# bristol_longshot.net
KiCad netlist of a schematic drawn in EAGLE
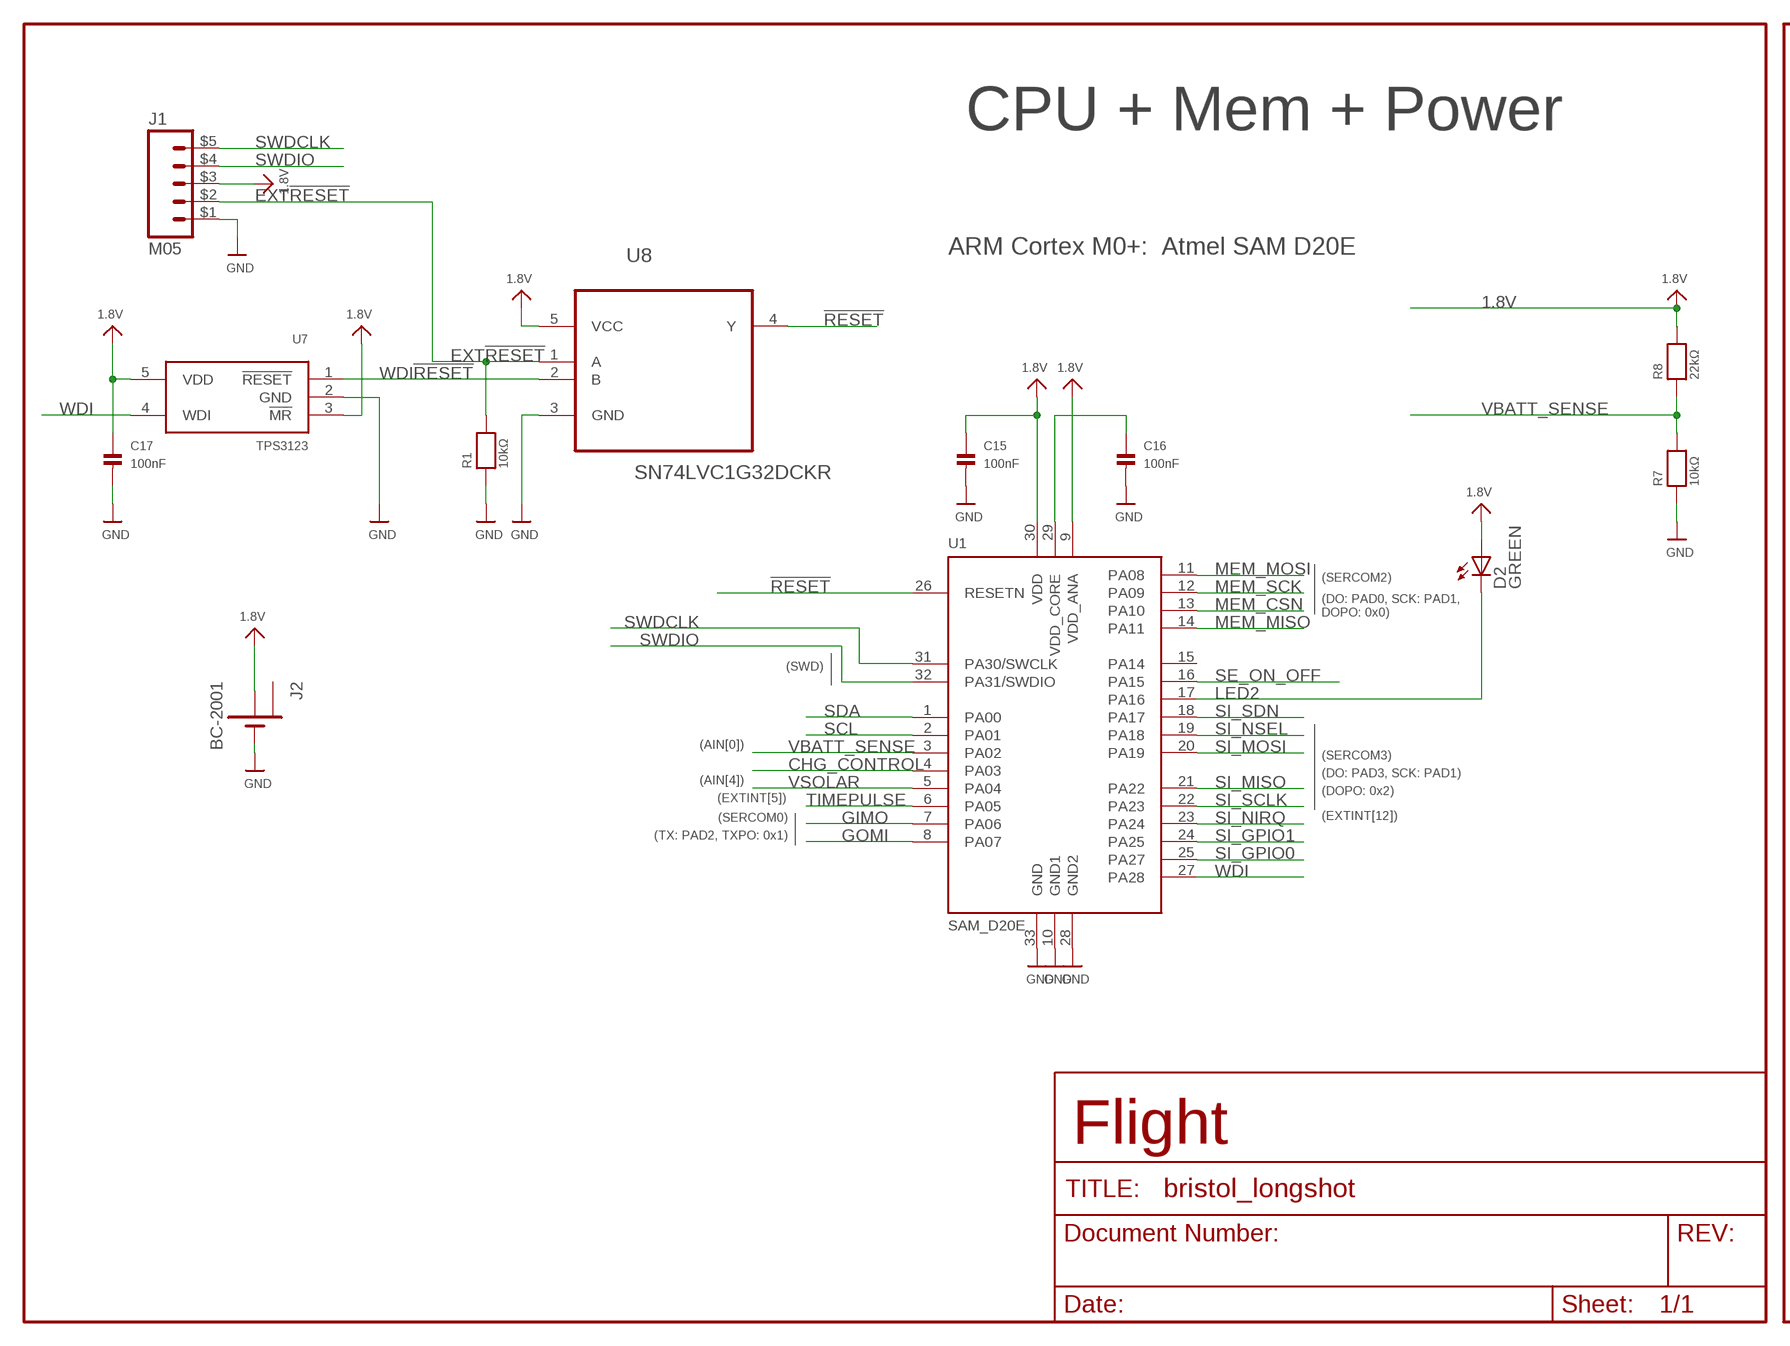
[diagram p0: schematic, sheet 1, part 1 of 2]
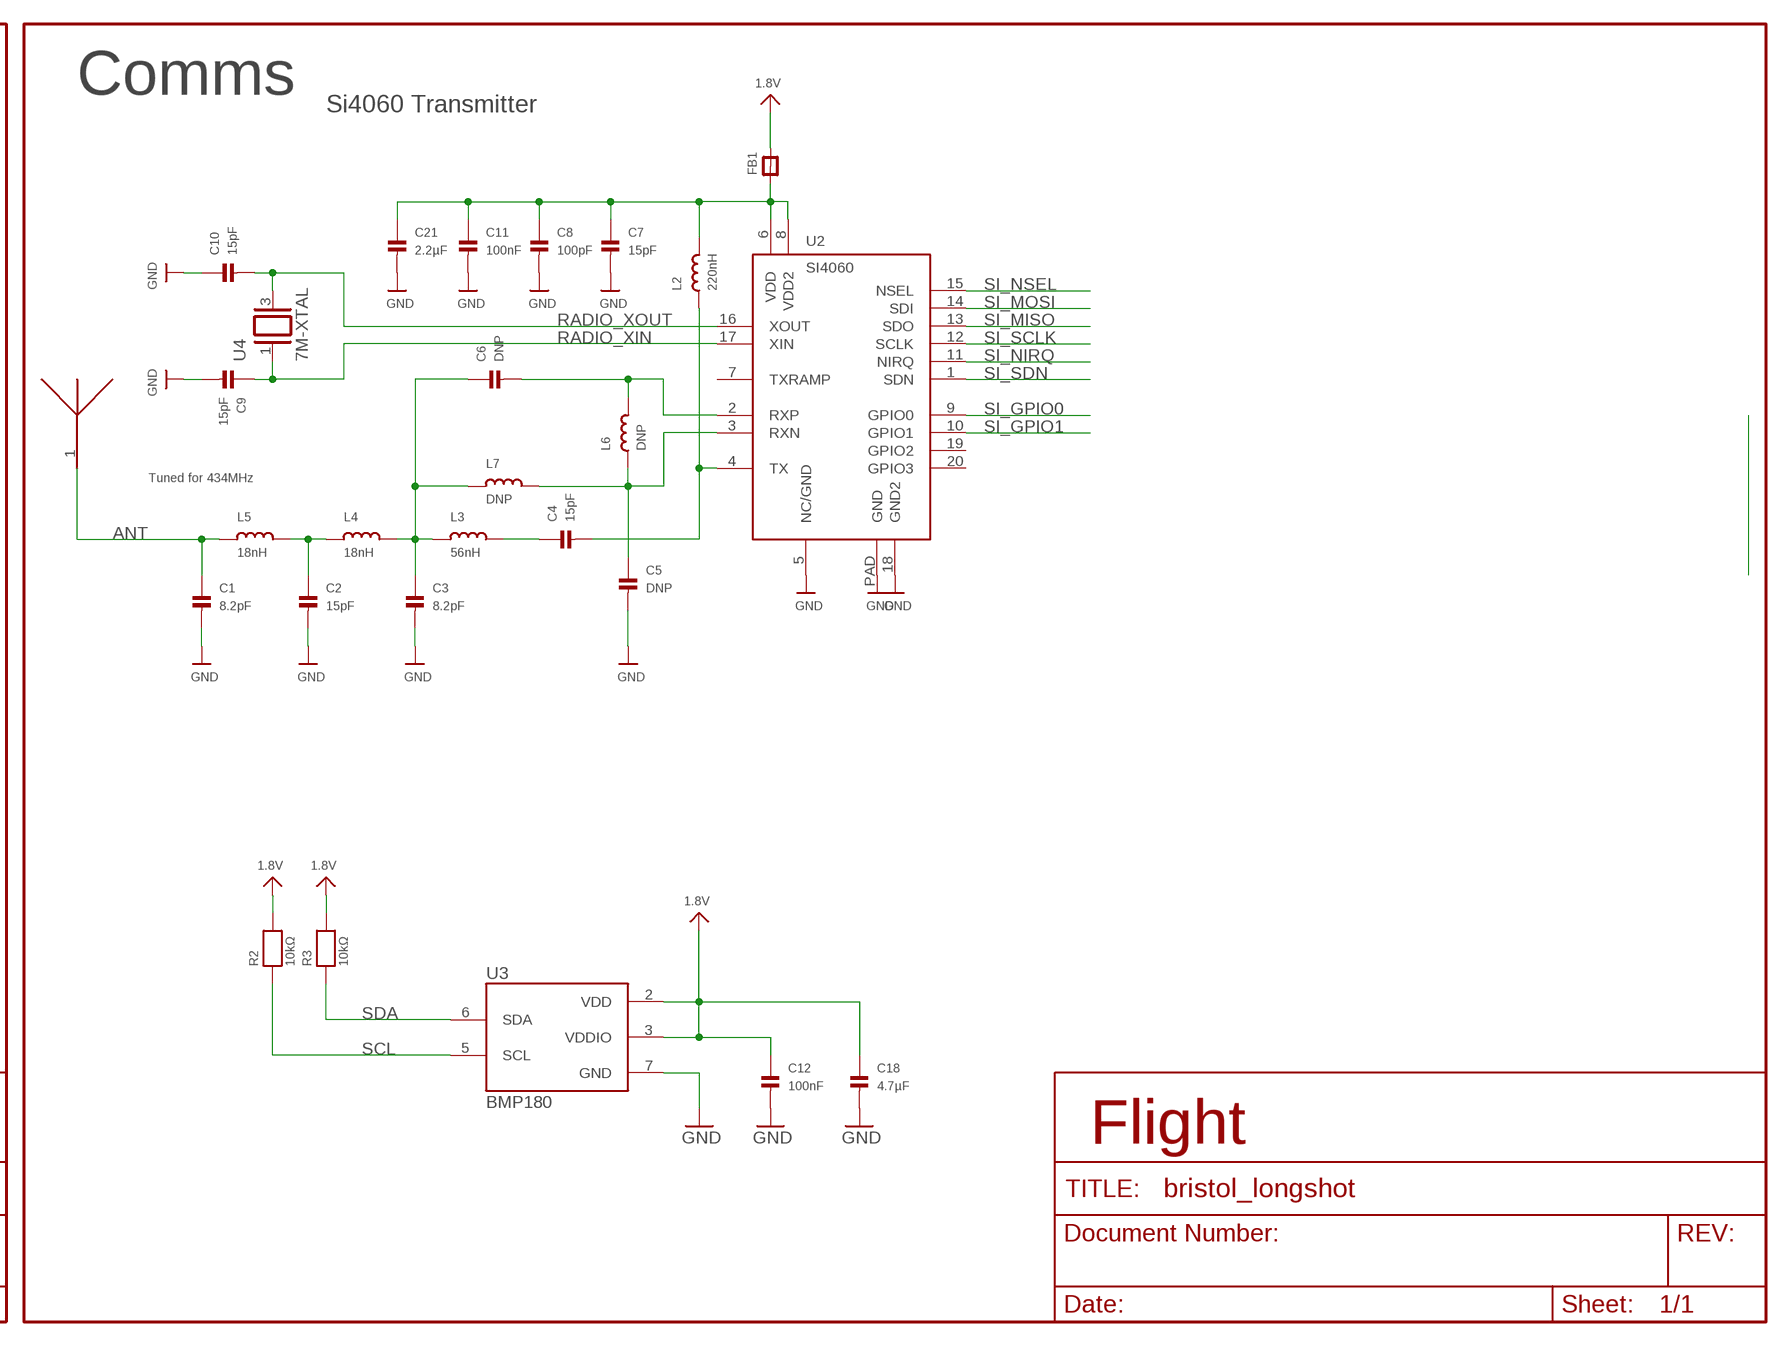
[diagram p1: schematic, sheet 1, part 2 of 2]

(export (version "E")
  (design (tool "Eeschema 10.0.6"))
  (components
    (comp (ref "C1")
      (value "8.2pF")
      (footprint "eagle-import:_0402")
      (libsource (lib "eagle-import") (part "CAP_CERAMIC_0402"))
    )
    (comp (ref "C2")
      (value "15pF")
      (footprint "eagle-import:_0402")
      (libsource (lib "eagle-import") (part "CAP_CERAMIC_0402"))
    )
    (comp (ref "C3")
      (value "8.2pF")
      (footprint "eagle-import:_0402")
      (libsource (lib "eagle-import") (part "CAP_CERAMIC_0402"))
    )
    (comp (ref "C4")
      (value "15pF")
      (footprint "eagle-import:_0402")
      (libsource (lib "eagle-import") (part "CAP_CERAMIC_0402"))
    )
    (comp (ref "C5")
      (value "DNP")
      (footprint "eagle-import:_0402")
      (libsource (lib "eagle-import") (part "CAP_CERAMIC_0402"))
    )
    (comp (ref "C6")
      (value "DNP")
      (footprint "eagle-import:_0402")
      (libsource (lib "eagle-import") (part "CAP_CERAMIC_0402"))
    )
    (comp (ref "C7")
      (value "15pF")
      (footprint "eagle-import:_0402")
      (libsource (lib "eagle-import") (part "CAP_CERAMIC_0402"))
    )
    (comp (ref "C8")
      (value "100pF")
      (footprint "eagle-import:_0402")
      (libsource (lib "eagle-import") (part "CAP_CERAMIC_0402"))
    )
    (comp (ref "C9")
      (value "15pF")
      (footprint "eagle-import:_0402")
      (libsource (lib "eagle-import") (part "CAP_CERAMIC_0402"))
    )
    (comp (ref "C10")
      (value "15pF")
      (footprint "eagle-import:_0402")
      (libsource (lib "eagle-import") (part "CAP_CERAMIC_0402"))
    )
    (comp (ref "C11")
      (value "100nF")
      (footprint "eagle-import:_0402")
      (libsource (lib "eagle-import") (part "CAP_CERAMIC_0402"))
    )
    (comp (ref "C12")
      (value "100nF")
      (footprint "eagle-import:_0402")
      (libsource (lib "eagle-import") (part "CAP_CERAMIC_0402"))
    )
    (comp (ref "C15")
      (value "100nF")
      (footprint "eagle-import:_0402")
      (libsource (lib "eagle-import") (part "CAP_CERAMIC_0402"))
    )
    (comp (ref "C16")
      (value "100nF")
      (footprint "eagle-import:_0402")
      (libsource (lib "eagle-import") (part "CAP_CERAMIC_0402"))
    )
    (comp (ref "C17")
      (value "100nF")
      (footprint "eagle-import:_0402")
      (libsource (lib "eagle-import") (part "CAP_CERAMIC_0402"))
    )
    (comp (ref "C18")
      (value "4.7µF")
      (footprint "eagle-import:_0402")
      (libsource (lib "eagle-import") (part "CAP_CERAMIC_0402"))
    )
    (comp (ref "C21")
      (value "2.2µF")
      (footprint "eagle-import:_0402")
      (libsource (lib "eagle-import") (part "CAP_CERAMIC_0402"))
    )
    (comp (ref "D2")
      (value "GREEN")
      (footprint "eagle-import:CHIPLED_0603")
      (libsource (lib "eagle-import") (part "LEDCHIPLED_0603"))
    )
    (comp (ref "FB1")
      (value "FERRITE_0402")
      (footprint "eagle-import:_0402")
      (libsource (lib "eagle-import") (part "FERRITE_0402"))
    )
    (comp (ref "J1")
      (value "M05")
      (footprint "eagle-import:M05_SIDE")
      (libsource (lib "eagle-import") (part "M05"))
    )
    (comp (ref "J2")
      (value "BC-2001")
      (footprint "eagle-import:BC-2001")
      (libsource (lib "eagle-import") (part "BC-2001"))
    )
    (comp (ref "L2")
      (value "220nH")
      (footprint "eagle-import:_0402")
      (libsource (lib "eagle-import") (part "INDUCTOR_0402"))
    )
    (comp (ref "L3")
      (value "56nH")
      (footprint "eagle-import:_0402")
      (libsource (lib "eagle-import") (part "INDUCTOR_0402"))
    )
    (comp (ref "L4")
      (value "18nH")
      (footprint "eagle-import:_0402")
      (libsource (lib "eagle-import") (part "INDUCTOR_0402"))
    )
    (comp (ref "L5")
      (value "18nH")
      (footprint "eagle-import:_0402")
      (libsource (lib "eagle-import") (part "INDUCTOR_0402"))
    )
    (comp (ref "L6")
      (value "DNP")
      (footprint "eagle-import:_0402")
      (libsource (lib "eagle-import") (part "INDUCTOR_0402"))
    )
    (comp (ref "L7")
      (value "DNP")
      (footprint "eagle-import:_0402")
      (libsource (lib "eagle-import") (part "INDUCTOR_0402"))
    )
    (comp (ref "R1")
      (value "10kΩ")
      (footprint "eagle-import:_0402")
      (libsource (lib "eagle-import") (part "RESISTOR_0402"))
    )
    (comp (ref "R2")
      (value "10kΩ")
      (footprint "eagle-import:_0402")
      (libsource (lib "eagle-import") (part "RESISTOR_0402"))
    )
    (comp (ref "R3")
      (value "10kΩ")
      (footprint "eagle-import:_0402")
      (libsource (lib "eagle-import") (part "RESISTOR_0402"))
    )
    (comp (ref "R7")
      (value "10kΩ")
      (footprint "eagle-import:_0402")
      (libsource (lib "eagle-import") (part "RESISTOR_0402"))
    )
    (comp (ref "R8")
      (value "22kΩ")
      (footprint "eagle-import:_0402")
      (libsource (lib "eagle-import") (part "RESISTOR_0402"))
    )
    (comp (ref "U1")
      (value "SAM_D20E")
      (footprint "eagle-import:QFN32_5MM")
      (libsource (lib "eagle-import") (part "SAM_D20E"))
    )
    (comp (ref "U2")
      (value "SI4060")
      (footprint "eagle-import:QFN20")
      (libsource (lib "eagle-import") (part "SI4060"))
    )
    (comp (ref "U3")
      (value "BMP180")
      (footprint "eagle-import:BMP180")
      (libsource (lib "eagle-import") (part "BMP180"))
    )
    (comp (ref "U4")
      (value "7M-XTAL")
      (footprint "eagle-import:7M-XTAL")
      (libsource (lib "eagle-import") (part "7M-XTAL"))
    )
    (comp (ref "U5")
      (value "0433AT62A0020E")
      (footprint "eagle-import:0433AT62A0020E")
      (libsource (lib "eagle-import") (part "0433AT62A0020E"))
    )
    (comp (ref "U7")
      (value "TPS3123")
      (footprint "eagle-import:SOT23-5")
      (libsource (lib "eagle-import") (part "TPS3123"))
    )
    (comp (ref "U8")
      (value "SN74LVC1G32DCKR")
      (footprint "eagle-import:SOT65P210X110-5N")
      (libsource (lib "eagle-import") (part "SN74LVC1G32DCKR"))
    )
  )
  (nets
    (net (code "1") (name "/+2") (class "Default")
      (node (ref "J2") (pin "+VE2") (pinfunction "+2_+VE2") (pintype "power_in"))
    )
    (net (code "2") (name "/ANT") (class "Default")
      (node (ref "C1") (pin "1") (pinfunction "P$1_1") (pintype "passive"))
      (node (ref "L5") (pin "1") (pinfunction "1_1") (pintype "passive"))
      (node (ref "U5") (pin "1") (pinfunction "P$1_1") (pintype "bidirectional"))
    )
    (net (code "3") (name "/CHG_CONTROL") (class "Default")
      (node (ref "U1") (pin "4") (pinfunction "PA03_4") (pintype "bidirectional"))
    )
    (net (code "4") (name "/EXT~{RESET}") (class "Default")
      (node (ref "J1") (pin "$2") (pinfunction "2_$2") (pintype "passive"))
      (node (ref "R1") (pin "2") (pinfunction "2_2") (pintype "passive"))
      (node (ref "U8") (pin "1") (pinfunction "A_1") (pintype "input"))
    )
    (net (code "5") (name "/GIMO") (class "Default")
      (node (ref "U1") (pin "7") (pinfunction "PA06_7") (pintype "bidirectional"))
    )
    (net (code "6") (name "/GOMI") (class "Default")
      (node (ref "U1") (pin "8") (pinfunction "PA07_8") (pintype "bidirectional"))
    )
    (net (code "7") (name "/LED2") (class "Default")
      (node (ref "D2") (pin "C") (pinfunction "C_C") (pintype "passive"))
      (node (ref "U1") (pin "17") (pinfunction "PA16_17") (pintype "bidirectional"))
    )
    (net (code "8") (name "/MEM_CSN") (class "Default")
      (node (ref "U1") (pin "13") (pinfunction "PA10_13") (pintype "bidirectional"))
    )
    (net (code "9") (name "/MEM_MISO") (class "Default")
      (node (ref "U1") (pin "14") (pinfunction "PA11_14") (pintype "bidirectional"))
    )
    (net (code "10") (name "/MEM_MOSI") (class "Default")
      (node (ref "U1") (pin "11") (pinfunction "PA08_11") (pintype "bidirectional"))
    )
    (net (code "11") (name "/MEM_SCK") (class "Default")
      (node (ref "U1") (pin "12") (pinfunction "PA09_12") (pintype "bidirectional"))
    )
    (net (code "12") (name "/RADIO_XIN") (class "Default")
      (node (ref "C9") (pin "1") (pinfunction "P$1_1") (pintype "passive"))
      (node (ref "U2") (pin "17") (pinfunction "XIN_17") (pintype "input"))
      (node (ref "U4") (pin "1") (pinfunction "1_1") (pintype "passive"))
    )
    (net (code "13") (name "/RADIO_XOUT") (class "Default")
      (node (ref "C10") (pin "2") (pinfunction "P$2_2") (pintype "passive"))
      (node (ref "U2") (pin "16") (pinfunction "XOUT_16") (pintype "output"))
      (node (ref "U4") (pin "3") (pinfunction "2_3") (pintype "passive"))
    )
    (net (code "14") (name "/SCL") (class "Default")
      (node (ref "R2") (pin "1") (pinfunction "1_1") (pintype "passive"))
      (node (ref "U1") (pin "2") (pinfunction "PA01_2") (pintype "bidirectional"))
      (node (ref "U3") (pin "5") (pinfunction "SCL_5") (pintype "input"))
    )
    (net (code "15") (name "/SDA") (class "Default")
      (node (ref "R3") (pin "1") (pinfunction "1_1") (pintype "passive"))
      (node (ref "U1") (pin "1") (pinfunction "PA00_1") (pintype "bidirectional"))
      (node (ref "U3") (pin "6") (pinfunction "SDA_6") (pintype "bidirectional"))
    )
    (net (code "16") (name "/SE_ON_OFF") (class "Default")
      (node (ref "U1") (pin "16") (pinfunction "PA15_16") (pintype "bidirectional"))
    )
    (net (code "17") (name "/SI_GPIO0") (class "Default")
      (node (ref "U1") (pin "25") (pinfunction "PA27_25") (pintype "bidirectional"))
      (node (ref "U2") (pin "9") (pinfunction "GPIO0_9") (pintype "bidirectional"))
    )
    (net (code "18") (name "/SI_GPIO1") (class "Default")
      (node (ref "U1") (pin "24") (pinfunction "PA25_24") (pintype "bidirectional"))
      (node (ref "U2") (pin "10") (pinfunction "GPIO1_10") (pintype "bidirectional"))
    )
    (net (code "19") (name "/SI_MISO") (class "Default")
      (node (ref "U1") (pin "21") (pinfunction "PA22_21") (pintype "bidirectional"))
      (node (ref "U2") (pin "13") (pinfunction "SDO_13") (pintype "output"))
    )
    (net (code "20") (name "/SI_MOSI") (class "Default")
      (node (ref "U1") (pin "20") (pinfunction "PA19_20") (pintype "bidirectional"))
      (node (ref "U2") (pin "14") (pinfunction "SDI_14") (pintype "bidirectional"))
    )
    (net (code "21") (name "/SI_NIRQ") (class "Default")
      (node (ref "U1") (pin "23") (pinfunction "PA24_23") (pintype "bidirectional"))
      (node (ref "U2") (pin "11") (pinfunction "NIRQ_11") (pintype "output"))
    )
    (net (code "22") (name "/SI_NSEL") (class "Default")
      (node (ref "U1") (pin "19") (pinfunction "PA18_19") (pintype "bidirectional"))
      (node (ref "U2") (pin "15") (pinfunction "NSEL_15") (pintype "input"))
    )
    (net (code "23") (name "/SI_SCLK") (class "Default")
      (node (ref "U1") (pin "22") (pinfunction "PA23_22") (pintype "bidirectional"))
      (node (ref "U2") (pin "12") (pinfunction "SCLK_12") (pintype "input"))
    )
    (net (code "24") (name "/SI_SDN") (class "Default")
      (node (ref "U1") (pin "18") (pinfunction "PA17_18") (pintype "bidirectional"))
      (node (ref "U2") (pin "1") (pinfunction "SDN_1") (pintype "input"))
    )
    (net (code "25") (name "/SWDCLK") (class "Default")
      (node (ref "J1") (pin "$5") (pinfunction "5_$5") (pintype "passive"))
      (node (ref "U1") (pin "31") (pinfunction "PA30/SWCLK_31") (pintype "bidirectional"))
    )
    (net (code "26") (name "/SWDIO") (class "Default")
      (node (ref "J1") (pin "$4") (pinfunction "4_$4") (pintype "passive"))
      (node (ref "U1") (pin "32") (pinfunction "PA31/SWDIO_32") (pintype "bidirectional"))
    )
    (net (code "27") (name "/TIMEPULSE") (class "Default")
      (node (ref "U1") (pin "6") (pinfunction "PA05_6") (pintype "bidirectional"))
    )
    (net (code "28") (name "/VBATT_SENSE") (class "Default")
      (node (ref "R7") (pin "2") (pinfunction "2_2") (pintype "passive"))
      (node (ref "R8") (pin "1") (pinfunction "1_1") (pintype "passive"))
      (node (ref "U1") (pin "3") (pinfunction "PA02_3") (pintype "bidirectional"))
    )
    (net (code "29") (name "/VSOLAR") (class "Default")
      (node (ref "U1") (pin "5") (pinfunction "PA04_5") (pintype "bidirectional"))
    )
    (net (code "30") (name "/WDI") (class "Default")
      (node (ref "U1") (pin "27") (pinfunction "PA28_27") (pintype "bidirectional"))
      (node (ref "U7") (pin "4") (pinfunction "WDI_4") (pintype "bidirectional"))
    )
    (net (code "31") (name "/WDI~{RESET}") (class "Default")
      (node (ref "U7") (pin "1") (pinfunction "~{RESET}_1") (pintype "bidirectional"))
      (node (ref "U8") (pin "2") (pinfunction "B_2") (pintype "input"))
    )
    (net (code "32") (name "/~{RESET}") (class "Default")
      (node (ref "U1") (pin "26") (pinfunction "RESETN_26") (pintype "input"))
      (node (ref "U8") (pin "4") (pinfunction "Y_4") (pintype "output"))
    )
    (net (code "33") (name "1.8V") (class "Default")
      (node (ref "C12") (pin "1") (pinfunction "P$1_1") (pintype "passive"))
      (node (ref "C15") (pin "1") (pinfunction "P$1_1") (pintype "passive"))
      (node (ref "C17") (pin "1") (pinfunction "P$1_1") (pintype "passive"))
      (node (ref "C18") (pin "1") (pinfunction "P$1_1") (pintype "passive"))
      (node (ref "D2") (pin "A") (pinfunction "A_A") (pintype "passive"))
      (node (ref "FB1") (pin "2") (pinfunction "P$2_2") (pintype "passive"))
      (node (ref "J1") (pin "$3") (pinfunction "3_$3") (pintype "passive"))
      (node (ref "J2") (pin "+VE1") (pinfunction "+_+VE1") (pintype "power_in"))
      (node (ref "R2") (pin "2") (pinfunction "2_2") (pintype "passive"))
      (node (ref "R3") (pin "2") (pinfunction "2_2") (pintype "passive"))
      (node (ref "R8") (pin "2") (pinfunction "2_2") (pintype "passive"))
      (node (ref "U1") (pin "30") (pinfunction "VDD_30") (pintype "power_in"))
      (node (ref "U1") (pin "9") (pinfunction "VDD_ANA_9") (pintype "power_in"))
      (node (ref "U3") (pin "2") (pinfunction "VDD_2") (pintype "power_in"))
      (node (ref "U3") (pin "3") (pinfunction "VDDIO_3") (pintype "power_in"))
      (node (ref "U7") (pin "3") (pinfunction "~{MR}_3") (pintype "bidirectional"))
      (node (ref "U7") (pin "5") (pinfunction "VDD_5") (pintype "bidirectional"))
      (node (ref "U8") (pin "5") (pinfunction "VCC_5") (pintype "power_in"))
    )
    (net (code "34") (name "GND") (class "Default")
      (node (ref "C1") (pin "2") (pinfunction "P$2_2") (pintype "passive"))
      (node (ref "C10") (pin "1") (pinfunction "P$1_1") (pintype "passive"))
      (node (ref "C11") (pin "2") (pinfunction "P$2_2") (pintype "passive"))
      (node (ref "C12") (pin "2") (pinfunction "P$2_2") (pintype "passive"))
      (node (ref "C15") (pin "2") (pinfunction "P$2_2") (pintype "passive"))
      (node (ref "C16") (pin "2") (pinfunction "P$2_2") (pintype "passive"))
      (node (ref "C17") (pin "2") (pinfunction "P$2_2") (pintype "passive"))
      (node (ref "C18") (pin "2") (pinfunction "P$2_2") (pintype "passive"))
      (node (ref "C2") (pin "2") (pinfunction "P$2_2") (pintype "passive"))
      (node (ref "C21") (pin "2") (pinfunction "P$2_2") (pintype "passive"))
      (node (ref "C3") (pin "2") (pinfunction "P$2_2") (pintype "passive"))
      (node (ref "C5") (pin "2") (pinfunction "P$2_2") (pintype "passive"))
      (node (ref "C7") (pin "2") (pinfunction "P$2_2") (pintype "passive"))
      (node (ref "C8") (pin "2") (pinfunction "P$2_2") (pintype "passive"))
      (node (ref "C9") (pin "2") (pinfunction "P$2_2") (pintype "passive"))
      (node (ref "J1") (pin "$1") (pinfunction "1_$1") (pintype "passive"))
      (node (ref "J2") (pin "-VE") (pinfunction "-_-VE") (pintype "power_in"))
      (node (ref "R1") (pin "1") (pinfunction "1_1") (pintype "passive"))
      (node (ref "R7") (pin "1") (pinfunction "1_1") (pintype "passive"))
      (node (ref "U1") (pin "10") (pinfunction "GND1_10") (pintype "power_in"))
      (node (ref "U1") (pin "28") (pinfunction "GND2_28") (pintype "power_in"))
      (node (ref "U1") (pin "33") (pinfunction "GND_33") (pintype "power_in"))
      (node (ref "U2") (pin "18") (pinfunction "GND2_18") (pintype "power_in"))
      (node (ref "U2") (pin "5") (pinfunction "NC/GND_5") (pintype "bidirectional"))
      (node (ref "U2") (pin "PAD") (pinfunction "GND_PAD") (pintype "power_in"))
      (node (ref "U3") (pin "7") (pinfunction "GND_7") (pintype "power_in"))
      (node (ref "U7") (pin "2") (pinfunction "GND_2") (pintype "bidirectional"))
      (node (ref "U8") (pin "3") (pinfunction "GND_3") (pintype "passive"))
    )
    (net (code "35") (name "Net-(C2-P$1)") (class "Default")
      (node (ref "C2") (pin "1") (pinfunction "P$1_1") (pintype "passive"))
      (node (ref "L4") (pin "1") (pinfunction "1_1") (pintype "passive"))
      (node (ref "L5") (pin "2") (pinfunction "2_2") (pintype "passive"))
    )
    (net (code "36") (name "Net-(C3-P$1)") (class "Default")
      (node (ref "C3") (pin "1") (pinfunction "P$1_1") (pintype "passive"))
      (node (ref "C6") (pin "1") (pinfunction "P$1_1") (pintype "passive"))
      (node (ref "L3") (pin "1") (pinfunction "1_1") (pintype "passive"))
      (node (ref "L4") (pin "2") (pinfunction "2_2") (pintype "passive"))
      (node (ref "L7") (pin "1") (pinfunction "1_1") (pintype "passive"))
    )
    (net (code "37") (name "Net-(C4-P$1)") (class "Default")
      (node (ref "C4") (pin "1") (pinfunction "P$1_1") (pintype "passive"))
      (node (ref "L3") (pin "2") (pinfunction "2_2") (pintype "passive"))
    )
    (net (code "38") (name "Net-(C4-P$2)") (class "Default")
      (node (ref "C4") (pin "2") (pinfunction "P$2_2") (pintype "passive"))
      (node (ref "L2") (pin "1") (pinfunction "1_1") (pintype "passive"))
      (node (ref "U2") (pin "4") (pinfunction "TX_4") (pintype "output"))
    )
    (net (code "39") (name "Net-(C5-P$1)") (class "Default")
      (node (ref "C5") (pin "1") (pinfunction "P$1_1") (pintype "passive"))
      (node (ref "L6") (pin "1") (pinfunction "1_1") (pintype "passive"))
      (node (ref "L7") (pin "2") (pinfunction "2_2") (pintype "passive"))
      (node (ref "U2") (pin "3") (pinfunction "RXN_3") (pintype "input"))
    )
    (net (code "40") (name "Net-(C6-P$2)") (class "Default")
      (node (ref "C6") (pin "2") (pinfunction "P$2_2") (pintype "passive"))
      (node (ref "L6") (pin "2") (pinfunction "2_2") (pintype "passive"))
      (node (ref "U2") (pin "2") (pinfunction "RXP_2") (pintype "input"))
    )
    (net (code "41") (name "Net-(C11-P$1)") (class "Default")
      (node (ref "C11") (pin "1") (pinfunction "P$1_1") (pintype "passive"))
      (node (ref "C21") (pin "1") (pinfunction "P$1_1") (pintype "passive"))
      (node (ref "C7") (pin "1") (pinfunction "P$1_1") (pintype "passive"))
      (node (ref "C8") (pin "1") (pinfunction "P$1_1") (pintype "passive"))
      (node (ref "FB1") (pin "1") (pinfunction "P$1_1") (pintype "passive"))
      (node (ref "L2") (pin "2") (pinfunction "2_2") (pintype "passive"))
      (node (ref "U2") (pin "6") (pinfunction "VDD_6") (pintype "power_in"))
      (node (ref "U2") (pin "8") (pinfunction "VDD2_8") (pintype "power_in"))
    )
    (net (code "42") (name "Net-(C16-P$1)") (class "Default")
      (node (ref "C16") (pin "1") (pinfunction "P$1_1") (pintype "passive"))
      (node (ref "U1") (pin "29") (pinfunction "VDD_CORE_29") (pintype "power_in"))
    )
    (net (code "43") (name "unconnected-(U1-PA14-Pad15)") (class "Default")
      (node (ref "U1") (pin "15") (pinfunction "PA14_15") (pintype "bidirectional"))
    )
    (net (code "44") (name "unconnected-(U2-GPIO2-Pad19)") (class "Default")
      (node (ref "U2") (pin "19") (pinfunction "GPIO2_19") (pintype "bidirectional"))
    )
    (net (code "45") (name "unconnected-(U2-GPIO3-Pad20)") (class "Default")
      (node (ref "U2") (pin "20") (pinfunction "GPIO3_20") (pintype "bidirectional"))
    )
    (net (code "46") (name "unconnected-(U2-TXRAMP-Pad7)") (class "Default")
      (node (ref "U2") (pin "7") (pinfunction "TXRAMP_7") (pintype "bidirectional"))
    )
  )
)
